# LM_HTR_001.net
KiCad netlist of a schematic drawn in Altium Designer
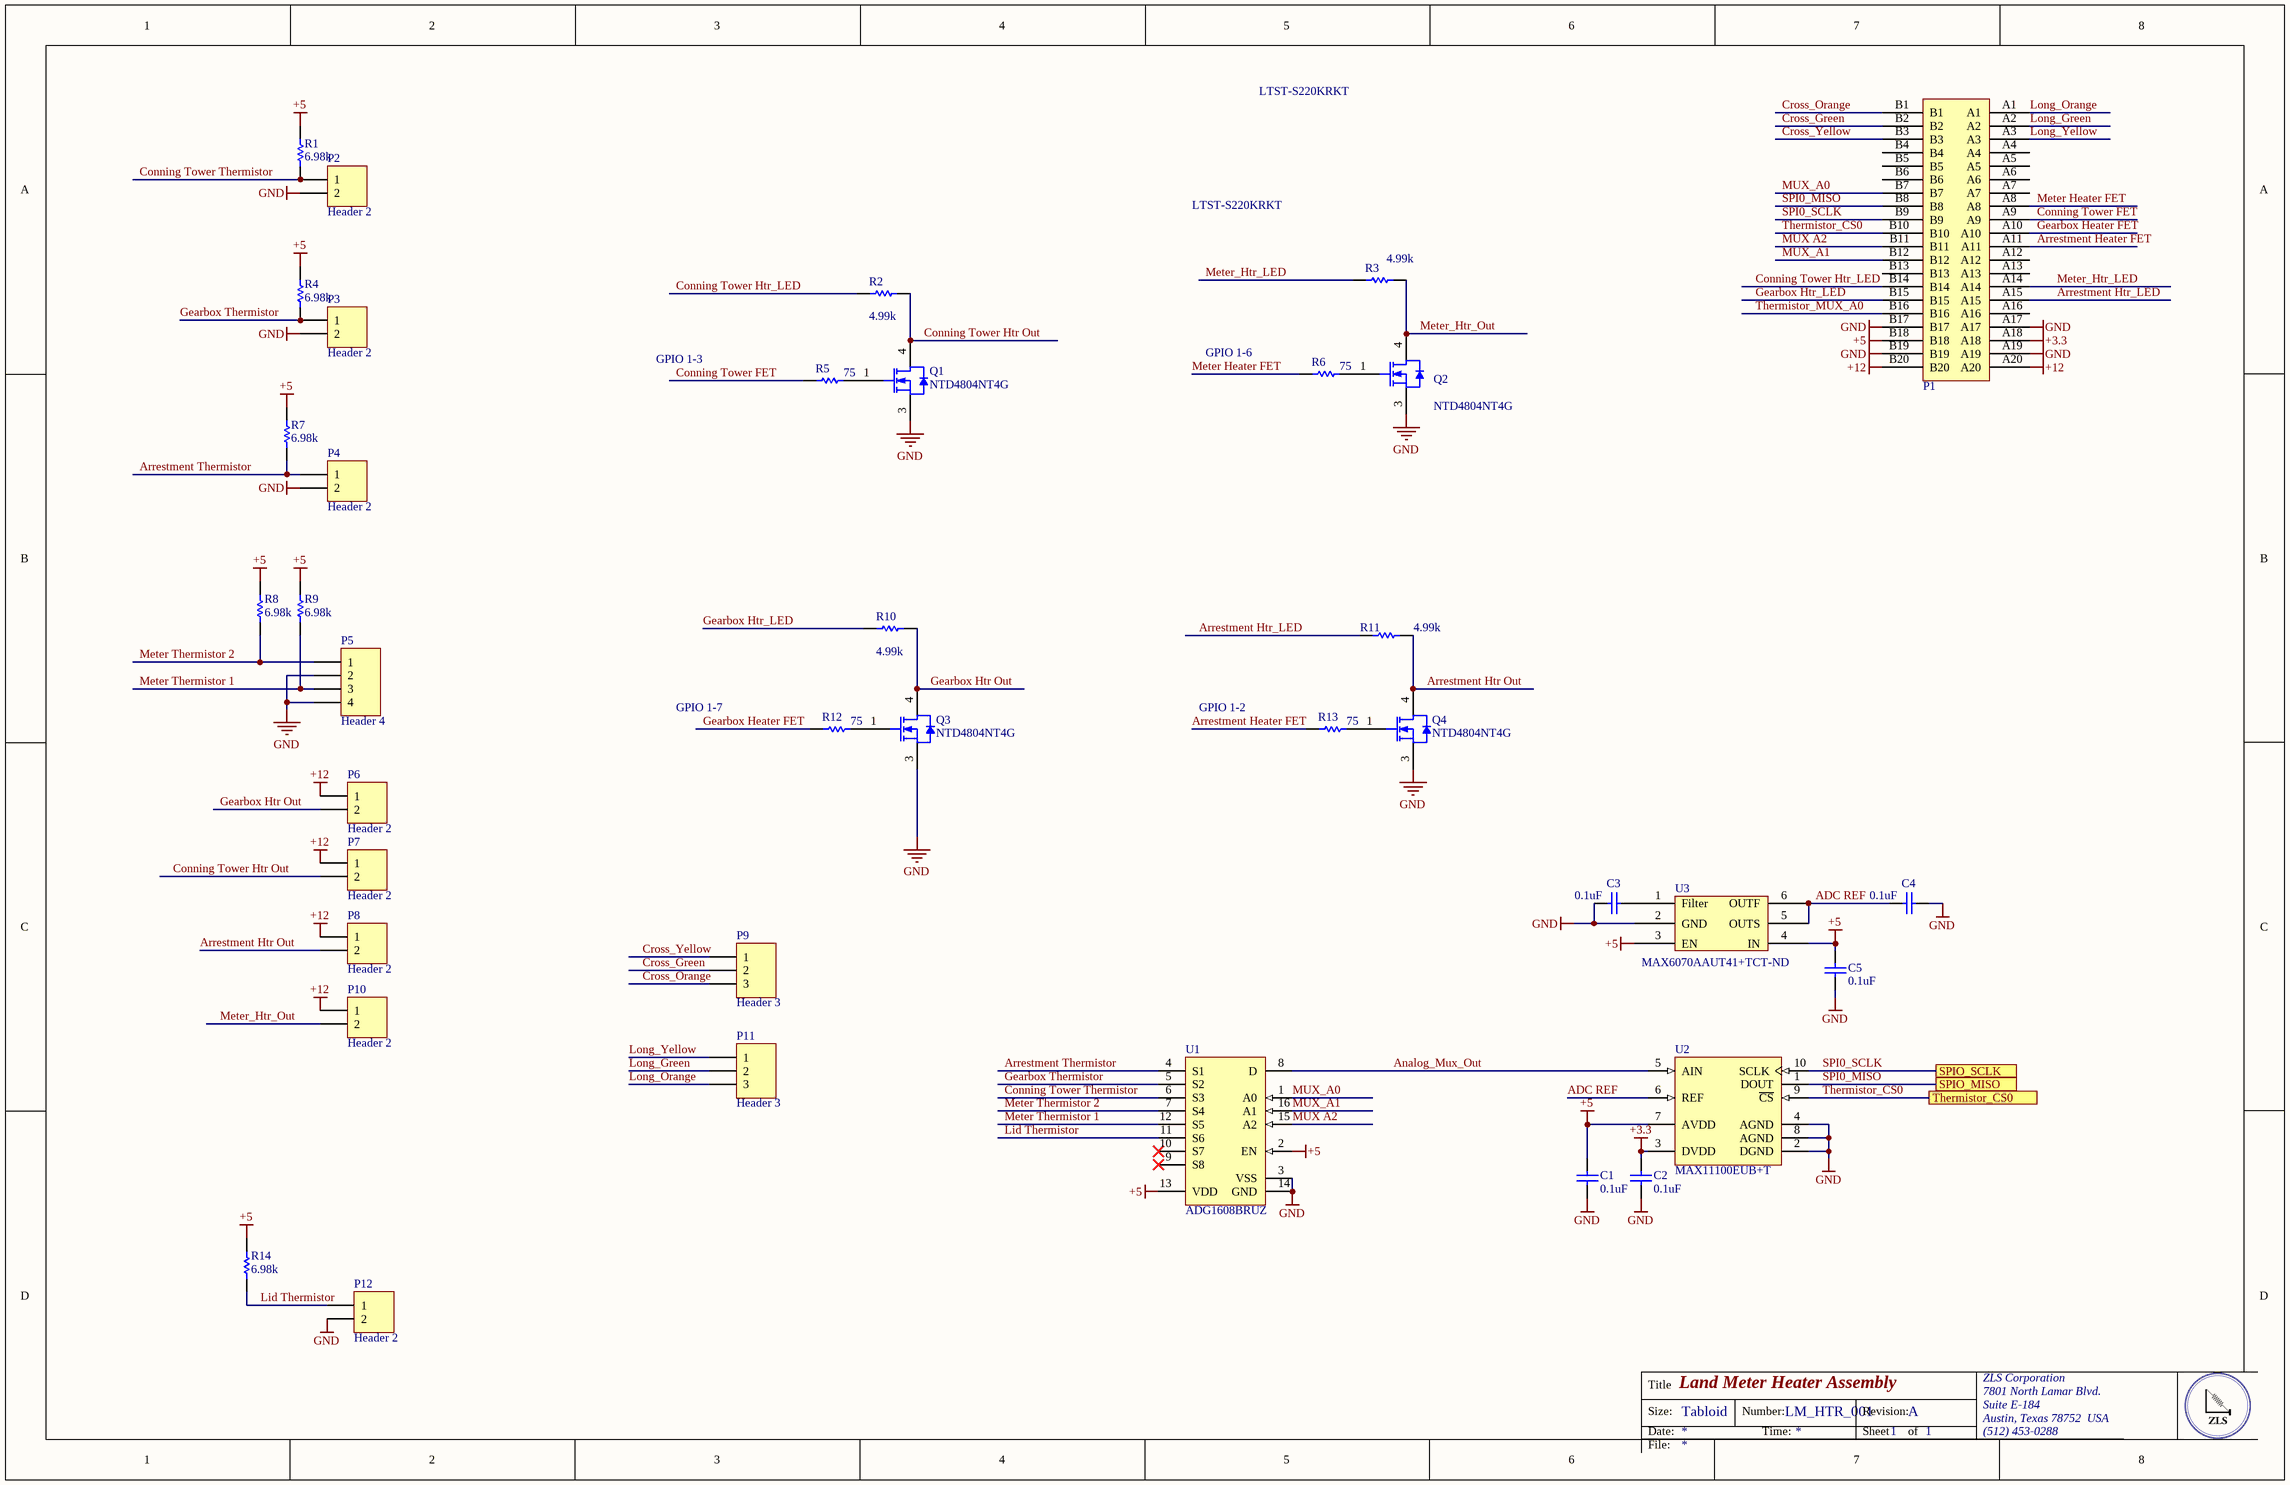
[diagram p0: LM_HTR_001.SchDoc]

(export (version "E")
  (design (tool "Eeschema 10.0.6"))
  (components
    (comp (ref "C1")
      (value "0.1uF")
      (footprint "CAPC0402(1005)60_L")
      (description "CAP CER 0.1UF 10V X7R 0402")
      (fields
        (field (name "MANUFACTURER") "Murata Electronics North America")
        (field (name "MANUFACTURER PART NUMBER") "GRM155R71A104KA01D")
      )
      (libsource (lib "Altium Content Vault") (part "CMP-1034-00252-1"))
    )
    (comp (ref "C2")
      (value "0.1uF")
      (footprint "CAPC0402(1005)60_L")
      (description "CAP CER 0.1UF 10V X7R 0402")
      (fields
        (field (name "MANUFACTURER") "Murata Electronics North America")
        (field (name "MANUFACTURER PART NUMBER") "GRM155R71A104KA01D")
      )
      (libsource (lib "Altium Content Vault") (part "CMP-1034-00252-1"))
    )
    (comp (ref "C3")
      (value "0.1uF")
      (footprint "CAPC0402(1005)60_L")
      (description "CAP CER 0.1UF 10V X7R 0402")
      (fields
        (field (name "MANUFACTURER") "Murata Electronics North America")
        (field (name "MANUFACTURER PART NUMBER") "GRM155R71A104KA01D")
      )
      (libsource (lib "Altium Content Vault") (part "CMP-1034-00252-1"))
    )
    (comp (ref "C4")
      (value "0.1uF")
      (footprint "CAPC0402(1005)60_L")
      (description "CAP CER 0.1UF 10V X7R 0402")
      (fields
        (field (name "MANUFACTURER") "Murata Electronics North America")
        (field (name "MANUFACTURER PART NUMBER") "GRM155R71A104KA01D")
      )
      (libsource (lib "Altium Content Vault") (part "CMP-1034-00252-1"))
    )
    (comp (ref "C5")
      (value "0.1uF")
      (footprint "CAPC0402(1005)60_L")
      (description "CAP CER 0.1UF 10V X7R 0402")
      (fields
        (field (name "MANUFACTURER") "Murata Electronics North America")
        (field (name "MANUFACTURER PART NUMBER") "GRM155R71A104KA01D")
      )
      (libsource (lib "Altium Content Vault") (part "CMP-1034-00252-1"))
    )
    (comp (ref "P1")
      (value "MEC6-120-02-PCB_")
      (footprint "MEC6-120-02-PCB")
      (libsource (lib "ZLS_Schematic_lib") (part "MEC6-120-02-PCB_"))
    )
    (comp (ref "P2")
      (value "Header 2")
      (footprint "HDR1X2")
      (description "Header, 2-Pin")
      (fields (field (name "PUBLISHER") "Altium Limited"))
      (libsource (lib "Miscellaneous Connectors") (part "Header 2"))
    )
    (comp (ref "P3")
      (value "Header 2")
      (footprint "HDR1X2")
      (description "Header, 2-Pin")
      (fields (field (name "PUBLISHER") "Altium Limited"))
      (libsource (lib "Miscellaneous Connectors") (part "Header 2"))
    )
    (comp (ref "P4")
      (value "Header 2")
      (footprint "HDR1X2")
      (description "Header, 2-Pin")
      (fields (field (name "PUBLISHER") "Altium Limited"))
      (libsource (lib "Miscellaneous Connectors") (part "Header 2"))
    )
    (comp (ref "P5")
      (value "Header 4")
      (footprint "HDR1X4")
      (description "Header, 4-Pin")
      (fields (field (name "PUBLISHER") "Altium Limited"))
      (libsource (lib "Miscellaneous Connectors") (part "Header 4"))
    )
    (comp (ref "P6")
      (value "Header 2")
      (footprint "HDR1X2")
      (description "Header, 2-Pin")
      (fields (field (name "PUBLISHER") "Altium Limited"))
      (libsource (lib "Miscellaneous Connectors") (part "Header 2"))
    )
    (comp (ref "P7")
      (value "Header 2")
      (footprint "HDR1X2")
      (description "Header, 2-Pin")
      (fields (field (name "PUBLISHER") "Altium Limited"))
      (libsource (lib "Miscellaneous Connectors") (part "Header 2"))
    )
    (comp (ref "P8")
      (value "Header 2")
      (footprint "HDR1X2")
      (description "Header, 2-Pin")
      (fields (field (name "PUBLISHER") "Altium Limited"))
      (libsource (lib "Miscellaneous Connectors") (part "Header 2"))
    )
    (comp (ref "P9")
      (value "Header 3")
      (footprint "HDR1X3")
      (description "Header, 3-Pin")
      (fields (field (name "PUBLISHER") "Altium Limited"))
      (libsource (lib "Miscellaneous Connectors") (part "Header 3"))
    )
    (comp (ref "P10")
      (value "Header 2")
      (footprint "HDR1X2")
      (description "Header, 2-Pin")
      (fields (field (name "PUBLISHER") "Altium Limited"))
      (libsource (lib "Miscellaneous Connectors") (part "Header 2"))
    )
    (comp (ref "P11")
      (value "Header 3")
      (footprint "HDR1X3")
      (description "Header, 3-Pin")
      (fields (field (name "PUBLISHER") "Altium Limited"))
      (libsource (lib "Miscellaneous Connectors") (part "Header 3"))
    )
    (comp (ref "P12")
      (value "Header 2")
      (footprint "HDR1X2")
      (description "Header, 2-Pin")
      (fields (field (name "PUBLISHER") "Altium Limited"))
      (libsource (lib "Miscellaneous Connectors") (part "Header 2"))
    )
    (comp (ref "Q1")
      (value "NTD4804NT4G")
      (footprint "ONSC-DPAK-3-369AA-01_V")
      (description "Power MOSFET, 30 V, 117 A, Single N-Channel, 3-Pin DPAK, Pb-Free, Tape and Reel")
      (fields (field (name "MANUFACTURER") "On Semiconductor"))
      (libsource (lib "Altium Content Vault") (part "CMP-1058-00341-1"))
    )
    (comp (ref "Q2")
      (value "NTD4804NT4G")
      (footprint "ONSC-DPAK-3-369AA-01_V")
      (description "Power MOSFET, 30 V, 117 A, Single N-Channel, 3-Pin DPAK, Pb-Free, Tape and Reel")
      (fields (field (name "MANUFACTURER") "On Semiconductor"))
      (libsource (lib "Altium Content Vault") (part "CMP-1058-00341-1"))
    )
    (comp (ref "Q3")
      (value "NTD4804NT4G")
      (footprint "ONSC-DPAK-3-369AA-01_V")
      (description "Power MOSFET, 30 V, 117 A, Single N-Channel, 3-Pin DPAK, Pb-Free, Tape and Reel")
      (fields (field (name "MANUFACTURER") "On Semiconductor"))
      (libsource (lib "Altium Content Vault") (part "CMP-1058-00341-1"))
    )
    (comp (ref "Q4")
      (value "NTD4804NT4G")
      (footprint "ONSC-DPAK-3-369AA-01_V")
      (description "Power MOSFET, 30 V, 117 A, Single N-Channel, 3-Pin DPAK, Pb-Free, Tape and Reel")
      (fields (field (name "MANUFACTURER") "On Semiconductor"))
      (libsource (lib "Altium Content Vault") (part "CMP-1058-00341-1"))
    )
    (comp (ref "R1")
      (value "6K98 1% 0805(2012)")
      (footprint "RESC0805(2012)_N")
      (description "6K98 0.125W 1% 0805 (2012 Metric)  SMD")
      (fields
        (field (name "MANUFACTURER") "Vishay Dale")
        (field (name "MANUFACTURER PART NUMBER") "CRCW08056K98FKEA")
        (field (name "RESISTANCE (OHMS)") "6.98k")
      )
      (libsource (lib "Altium Content Vault") (part "CMP-1013-00606-1"))
    )
    (comp (ref "R2")
      (value "~")
      (footprint "RESC0805(2012)_L")
      (fields
        (field (name "MANUFACTURER") "Vishay Dale")
        (field (name "MANUFACTURER PART NUMBER") "CRCW08054K99FKEA")
        (field (name "RESISTANCE (OHMS)") "4.99k")
        (field (name "TOLERANCE") "±1%")
      )
      (libsource (lib "Altium Content Vault") (part "CMP-1013-00393-1"))
    )
    (comp (ref "R3")
      (value "~")
      (footprint "RESC0805(2012)_L")
      (fields
        (field (name "MANUFACTURER") "Vishay Dale")
        (field (name "MANUFACTURER PART NUMBER") "CRCW08054K99FKEA")
        (field (name "RESISTANCE (OHMS)") "4.99k")
        (field (name "TOLERANCE") "±1%")
      )
      (libsource (lib "Altium Content Vault") (part "CMP-1013-00393-1"))
    )
    (comp (ref "R4")
      (value "6K98 1% 0805(2012)")
      (footprint "RESC0805(2012)_N")
      (description "6K98 0.125W 1% 0805 (2012 Metric)  SMD")
      (fields
        (field (name "MANUFACTURER") "Vishay Dale")
        (field (name "MANUFACTURER PART NUMBER") "CRCW08056K98FKEA")
        (field (name "RESISTANCE (OHMS)") "6.98k")
      )
      (libsource (lib "Altium Content Vault") (part "CMP-1013-00606-1"))
    )
    (comp (ref "R5")
      (value "~")
      (footprint "RESC0805(2012)_L")
      (fields
        (field (name "MANUFACTURER") "Vishay Dale")
        (field (name "MANUFACTURER PART NUMBER") "CRCW080575R0FKEA")
        (field (name "RESISTANCE (OHMS)") "75")
        (field (name "TOLERANCE") "±1%")
      )
      (libsource (lib "Altium Content Vault") (part "CMP-1013-00393-1"))
    )
    (comp (ref "R6")
      (value "~")
      (footprint "RESC0805(2012)_L")
      (fields
        (field (name "MANUFACTURER") "Vishay Dale")
        (field (name "MANUFACTURER PART NUMBER") "CRCW080575R0FKEA")
        (field (name "RESISTANCE (OHMS)") "75")
        (field (name "TOLERANCE") "±1%")
      )
      (libsource (lib "Altium Content Vault") (part "CMP-1013-00393-1"))
    )
    (comp (ref "R7")
      (value "6K98 1% 0805(2012)")
      (footprint "RESC0805(2012)_N")
      (description "6K98 0.125W 1% 0805 (2012 Metric)  SMD")
      (fields
        (field (name "MANUFACTURER") "Vishay Dale")
        (field (name "MANUFACTURER PART NUMBER") "CRCW08056K98FKEA")
        (field (name "RESISTANCE (OHMS)") "6.98k")
      )
      (libsource (lib "Altium Content Vault") (part "CMP-1013-00606-1"))
    )
    (comp (ref "R8")
      (value "6K98 1% 0805(2012)")
      (footprint "RESC0805(2012)_N")
      (description "6K98 0.125W 1% 0805 (2012 Metric)  SMD")
      (fields
        (field (name "MANUFACTURER") "Vishay Dale")
        (field (name "MANUFACTURER PART NUMBER") "CRCW08056K98FKEA")
        (field (name "RESISTANCE (OHMS)") "6.98k")
      )
      (libsource (lib "Altium Content Vault") (part "CMP-1013-00606-1"))
    )
    (comp (ref "R9")
      (value "6K98 1% 0805(2012)")
      (footprint "RESC0805(2012)_N")
      (description "6K98 0.125W 1% 0805 (2012 Metric)  SMD")
      (fields
        (field (name "MANUFACTURER") "Vishay Dale")
        (field (name "MANUFACTURER PART NUMBER") "CRCW08056K98FKEA")
        (field (name "RESISTANCE (OHMS)") "6.98k")
      )
      (libsource (lib "Altium Content Vault") (part "CMP-1013-00606-1"))
    )
    (comp (ref "R10")
      (value "~")
      (footprint "RESC0805(2012)_L")
      (fields
        (field (name "MANUFACTURER") "Vishay Dale")
        (field (name "MANUFACTURER PART NUMBER") "CRCW08054K99FKEA")
        (field (name "RESISTANCE (OHMS)") "4.99k")
        (field (name "TOLERANCE") "±1%")
      )
      (libsource (lib "Altium Content Vault") (part "CMP-1013-00393-1"))
    )
    (comp (ref "R11")
      (value "~")
      (footprint "RESC0805(2012)_L")
      (fields
        (field (name "MANUFACTURER") "Vishay Dale")
        (field (name "MANUFACTURER PART NUMBER") "CRCW08054K99FKEA")
        (field (name "RESISTANCE (OHMS)") "4.99k")
        (field (name "TOLERANCE") "±1%")
      )
      (libsource (lib "Altium Content Vault") (part "CMP-1013-00393-1"))
    )
    (comp (ref "R12")
      (value "~")
      (footprint "RESC0805(2012)_L")
      (fields
        (field (name "MANUFACTURER") "Vishay Dale")
        (field (name "MANUFACTURER PART NUMBER") "CRCW080575R0FKEA")
        (field (name "RESISTANCE (OHMS)") "75")
        (field (name "TOLERANCE") "±1%")
      )
      (libsource (lib "Altium Content Vault") (part "CMP-1013-00393-1"))
    )
    (comp (ref "R13")
      (value "~")
      (footprint "RESC0805(2012)_L")
      (fields
        (field (name "MANUFACTURER") "Vishay Dale")
        (field (name "MANUFACTURER PART NUMBER") "CRCW080575R0FKEA")
        (field (name "RESISTANCE (OHMS)") "75")
        (field (name "TOLERANCE") "±1%")
      )
      (libsource (lib "Altium Content Vault") (part "CMP-1013-00393-1"))
    )
    (comp (ref "R14")
      (value "6K98 1% 0805(2012)")
      (footprint "RESC0805(2012)_N")
      (description "6K98 0.125W 1% 0805 (2012 Metric)  SMD")
      (fields
        (field (name "MANUFACTURER") "Vishay Dale")
        (field (name "MANUFACTURER PART NUMBER") "CRCW08056K98FKEA")
        (field (name "RESISTANCE (OHMS)") "6.98k")
      )
      (libsource (lib "Altium Content Vault") (part "CMP-1013-00606-1"))
    )
    (comp (ref "U1")
      (value "ADG1608BRUZ")
      (footprint "ADI-RU-16_M")
      (description "4.5 Ohm Ron, 8-Channel +/-5 V,+12 V, +5 V and +3.3 V Multiplexer, 16-pin SOP (RU-16), Tube")
      (fields (field (name "MANUFACTURER") "Analog Devices"))
      (libsource (lib "Altium Content Vault") (part "ADI-ADG1608-RU-16"))
    )
    (comp (ref "U2")
      (value "MAX11100EUB+T")
      (footprint "U10+2_L")
      (description "16-Bit, +5V, 200ksps ADC with 10uA Shutdown, 10-Pin uMAX, -40°C to +85°C, Pb-Free, Tape and Reel")
      (libsource (lib "Altium Content Vault") (part "CON-ADC-MAX11100-IL10"))
    )
    (comp (ref "U3")
      (value "MAX6070AAUT41+T")
      (footprint "SOT95P280X445-6N")
      (description "IC VREF SERIES 4.096V SOT23")
      (fields
        (field (name "SUPPLIER PART NUMBER 1") "MAX6070AAUT41+TCT-ND")
        (field (name "MANUFACTURER") "Maxim Integrated")
        (field (name "TOLERANCE") "±0.04%")
      )
      (libsource (lib "ZLS_Schematic_lib") (part "MAX6070AAUT41+T"))
    )
  )
  (nets
    (net (code "1") (name "+3.3") (class "Default")
      (node (ref "C2") (pin "1") (pinfunction "1_1") (pintype "passive"))
      (node (ref "P1") (pin "A18") (pinfunction "A18_A18") (pintype "passive"))
      (node (ref "U2") (pin "3") (pinfunction "DVDD_3") (pintype "power_in"))
    )
    (net (code "2") (name "+5") (class "Default")
      (node (ref "C1") (pin "1") (pinfunction "1_1") (pintype "passive"))
      (node (ref "C5") (pin "1") (pinfunction "1_1") (pintype "passive"))
      (node (ref "P1") (pin "B18") (pinfunction "B18_B18") (pintype "passive"))
      (node (ref "R1") (pin "2") (pinfunction "2_2") (pintype "passive"))
      (node (ref "R14") (pin "1") (pinfunction "1_1") (pintype "passive"))
      (node (ref "R4") (pin "2") (pinfunction "2_2") (pintype "passive"))
      (node (ref "R7") (pin "1") (pinfunction "1_1") (pintype "passive"))
      (node (ref "R8") (pin "1") (pinfunction "1_1") (pintype "passive"))
      (node (ref "R9") (pin "2") (pinfunction "2_2") (pintype "passive"))
      (node (ref "U1") (pin "13") (pinfunction "VDD_13") (pintype "power_in"))
      (node (ref "U1") (pin "2") (pinfunction "EN_2") (pintype "input"))
      (node (ref "U2") (pin "7") (pinfunction "AVDD_7") (pintype "power_in"))
      (node (ref "U3") (pin "3") (pinfunction "EN_3") (pintype "passive"))
      (node (ref "U3") (pin "4") (pinfunction "IN_4") (pintype "passive"))
    )
    (net (code "3") (name "+12") (class "Default")
      (node (ref "P1") (pin "A20") (pinfunction "A20_A20") (pintype "passive"))
      (node (ref "P1") (pin "B20") (pinfunction "B20_B20") (pintype "passive"))
      (node (ref "P10") (pin "1") (pinfunction "1_1") (pintype "passive"))
      (node (ref "P6") (pin "1") (pinfunction "1_1") (pintype "passive"))
      (node (ref "P7") (pin "1") (pinfunction "1_1") (pintype "passive"))
      (node (ref "P8") (pin "1") (pinfunction "1_1") (pintype "passive"))
    )
    (net (code "4") (name "/ADC REF") (class "Default")
      (node (ref "C4") (pin "2") (pinfunction "2_2") (pintype "passive"))
      (node (ref "U2") (pin "6") (pinfunction "REF_6") (pintype "input"))
      (node (ref "U3") (pin "5") (pinfunction "OUTS_5") (pintype "passive"))
      (node (ref "U3") (pin "6") (pinfunction "OUTF_6") (pintype "passive"))
    )
    (net (code "5") (name "/Analog_Mux_Out") (class "Default")
      (node (ref "U1") (pin "8") (pinfunction "D_8") (pintype "passive"))
      (node (ref "U2") (pin "5") (pinfunction "AIN_5") (pintype "input"))
    )
    (net (code "6") (name "/Arrestment Heater FET") (class "Default")
      (node (ref "P1") (pin "A11") (pinfunction "A11_A11") (pintype "passive"))
      (node (ref "R13") (pin "1") (pinfunction "1_1") (pintype "passive"))
    )
    (net (code "7") (name "/Arrestment Htr Out") (class "Default")
      (node (ref "P8") (pin "2") (pinfunction "2_2") (pintype "passive"))
      (node (ref "Q4") (pin "4") (pinfunction "D_4") (pintype "passive"))
      (node (ref "R11") (pin "2") (pinfunction "2_2") (pintype "passive"))
    )
    (net (code "8") (name "/Arrestment Htr_LED") (class "Default")
      (node (ref "P1") (pin "A15") (pinfunction "A15_A15") (pintype "passive"))
      (node (ref "R11") (pin "1") (pinfunction "1_1") (pintype "passive"))
    )
    (net (code "9") (name "/Arrestment Thermistor") (class "Default")
      (node (ref "P4") (pin "1") (pinfunction "1_1") (pintype "passive"))
      (node (ref "R7") (pin "2") (pinfunction "2_2") (pintype "passive"))
      (node (ref "U1") (pin "4") (pinfunction "S1_4") (pintype "passive"))
    )
    (net (code "10") (name "/Conning Tower FET") (class "Default")
      (node (ref "P1") (pin "A9") (pinfunction "A9_A9") (pintype "passive"))
      (node (ref "R5") (pin "1") (pinfunction "1_1") (pintype "passive"))
    )
    (net (code "11") (name "/Conning Tower Htr Out") (class "Default")
      (node (ref "P7") (pin "2") (pinfunction "2_2") (pintype "passive"))
      (node (ref "Q1") (pin "4") (pinfunction "D_4") (pintype "passive"))
      (node (ref "R2") (pin "1") (pinfunction "1_1") (pintype "passive"))
    )
    (net (code "12") (name "/Conning Tower Htr_LED") (class "Default")
      (node (ref "P1") (pin "B14") (pinfunction "B14_B14") (pintype "passive"))
      (node (ref "R2") (pin "2") (pinfunction "2_2") (pintype "passive"))
    )
    (net (code "13") (name "/Conning Tower Thermistor") (class "Default")
      (node (ref "P2") (pin "1") (pinfunction "1_1") (pintype "passive"))
      (node (ref "R1") (pin "1") (pinfunction "1_1") (pintype "passive"))
      (node (ref "U1") (pin "6") (pinfunction "S3_6") (pintype "passive"))
    )
    (net (code "14") (name "/Cross_Green") (class "Default")
      (node (ref "P1") (pin "B2") (pinfunction "B2_B2") (pintype "passive"))
      (node (ref "P9") (pin "2") (pinfunction "2_2") (pintype "passive"))
    )
    (net (code "15") (name "/Cross_Orange") (class "Default")
      (node (ref "P1") (pin "B1") (pinfunction "B1_B1") (pintype "passive"))
      (node (ref "P9") (pin "3") (pinfunction "3_3") (pintype "passive"))
    )
    (net (code "16") (name "/Cross_Yellow") (class "Default")
      (node (ref "P1") (pin "B3") (pinfunction "B3_B3") (pintype "passive"))
      (node (ref "P9") (pin "1") (pinfunction "1_1") (pintype "passive"))
    )
    (net (code "17") (name "/Gearbox Heater FET") (class "Default")
      (node (ref "P1") (pin "A10") (pinfunction "A10_A10") (pintype "passive"))
      (node (ref "R12") (pin "1") (pinfunction "1_1") (pintype "passive"))
    )
    (net (code "18") (name "/Gearbox Htr Out") (class "Default")
      (node (ref "P6") (pin "2") (pinfunction "2_2") (pintype "passive"))
      (node (ref "Q3") (pin "4") (pinfunction "D_4") (pintype "passive"))
      (node (ref "R10") (pin "1") (pinfunction "1_1") (pintype "passive"))
    )
    (net (code "19") (name "/Gearbox Htr_LED") (class "Default")
      (node (ref "P1") (pin "B15") (pinfunction "B15_B15") (pintype "passive"))
      (node (ref "R10") (pin "2") (pinfunction "2_2") (pintype "passive"))
    )
    (net (code "20") (name "/Gearbox Thermistor") (class "Default")
      (node (ref "P3") (pin "1") (pinfunction "1_1") (pintype "passive"))
      (node (ref "R4") (pin "1") (pinfunction "1_1") (pintype "passive"))
      (node (ref "U1") (pin "5") (pinfunction "S2_5") (pintype "passive"))
    )
    (net (code "21") (name "/Lid Thermistor") (class "Default")
      (node (ref "P12") (pin "1") (pinfunction "1_1") (pintype "passive"))
      (node (ref "R14") (pin "2") (pinfunction "2_2") (pintype "passive"))
      (node (ref "U1") (pin "11") (pinfunction "S6_11") (pintype "passive"))
    )
    (net (code "22") (name "/Long_Green") (class "Default")
      (node (ref "P1") (pin "A2") (pinfunction "A2_A2") (pintype "passive"))
      (node (ref "P11") (pin "2") (pinfunction "2_2") (pintype "passive"))
    )
    (net (code "23") (name "/Long_Orange") (class "Default")
      (node (ref "P1") (pin "A1") (pinfunction "A1_A1") (pintype "passive"))
      (node (ref "P11") (pin "3") (pinfunction "3_3") (pintype "passive"))
    )
    (net (code "24") (name "/Long_Yellow") (class "Default")
      (node (ref "P1") (pin "A3") (pinfunction "A3_A3") (pintype "passive"))
      (node (ref "P11") (pin "1") (pinfunction "1_1") (pintype "passive"))
    )
    (net (code "25") (name "/MUX A2") (class "Default")
      (node (ref "P1") (pin "B11") (pinfunction "B11_B11") (pintype "passive"))
      (node (ref "U1") (pin "15") (pinfunction "A2_15") (pintype "input"))
    )
    (net (code "26") (name "/MUX_A0") (class "Default")
      (node (ref "P1") (pin "B7") (pinfunction "B7_B7") (pintype "passive"))
      (node (ref "U1") (pin "1") (pinfunction "A0_1") (pintype "input"))
    )
    (net (code "27") (name "/MUX_A1") (class "Default")
      (node (ref "P1") (pin "B12") (pinfunction "B12_B12") (pintype "passive"))
      (node (ref "U1") (pin "16") (pinfunction "A1_16") (pintype "input"))
    )
    (net (code "28") (name "/Meter Heater FET") (class "Default")
      (node (ref "P1") (pin "A8") (pinfunction "A8_A8") (pintype "passive"))
      (node (ref "R6") (pin "1") (pinfunction "1_1") (pintype "passive"))
    )
    (net (code "29") (name "/Meter Thermistor 1") (class "Default")
      (node (ref "P5") (pin "3") (pinfunction "3_3") (pintype "passive"))
      (node (ref "R9") (pin "1") (pinfunction "1_1") (pintype "passive"))
      (node (ref "U1") (pin "12") (pinfunction "S5_12") (pintype "passive"))
    )
    (net (code "30") (name "/Meter Thermistor 2") (class "Default")
      (node (ref "P5") (pin "1") (pinfunction "1_1") (pintype "passive"))
      (node (ref "R8") (pin "2") (pinfunction "2_2") (pintype "passive"))
      (node (ref "U1") (pin "7") (pinfunction "S4_7") (pintype "passive"))
    )
    (net (code "31") (name "/Meter_Htr_LED") (class "Default")
      (node (ref "P1") (pin "A14") (pinfunction "A14_A14") (pintype "passive"))
      (node (ref "R3") (pin "1") (pinfunction "1_1") (pintype "passive"))
    )
    (net (code "32") (name "/Meter_Htr_Out") (class "Default")
      (node (ref "P10") (pin "2") (pinfunction "2_2") (pintype "passive"))
      (node (ref "Q2") (pin "4") (pinfunction "D_4") (pintype "passive"))
      (node (ref "R3") (pin "2") (pinfunction "2_2") (pintype "passive"))
    )
    (net (code "33") (name "/SPI0_MISO") (class "Default")
      (node (ref "P1") (pin "B8") (pinfunction "B8_B8") (pintype "passive"))
      (node (ref "U2") (pin "1") (pinfunction "DOUT_1") (pintype "tri_state"))
    )
    (net (code "34") (name "/SPI0_SCLK") (class "Default")
      (node (ref "P1") (pin "B9") (pinfunction "B9_B9") (pintype "passive"))
      (node (ref "U2") (pin "10") (pinfunction "SCLK_10") (pintype "input"))
    )
    (net (code "35") (name "/Thermistor_CS0") (class "Default")
      (node (ref "P1") (pin "B10") (pinfunction "B10_B10") (pintype "passive"))
      (node (ref "U2") (pin "9") (pinfunction "~{CS}_9") (pintype "input"))
    )
    (net (code "36") (name "/Thermistor_MUX_A0") (class "Default")
      (node (ref "P1") (pin "B16") (pinfunction "B16_B16") (pintype "passive"))
    )
    (net (code "37") (name "GND") (class "Default")
      (node (ref "C1") (pin "2") (pinfunction "2_2") (pintype "passive"))
      (node (ref "C2") (pin "2") (pinfunction "2_2") (pintype "passive"))
      (node (ref "C3") (pin "2") (pinfunction "2_2") (pintype "passive"))
      (node (ref "C4") (pin "1") (pinfunction "1_1") (pintype "passive"))
      (node (ref "C5") (pin "2") (pinfunction "2_2") (pintype "passive"))
      (node (ref "P1") (pin "A17") (pinfunction "A17_A17") (pintype "passive"))
      (node (ref "P1") (pin "A19") (pinfunction "A19_A19") (pintype "passive"))
      (node (ref "P1") (pin "B17") (pinfunction "B17_B17") (pintype "passive"))
      (node (ref "P1") (pin "B19") (pinfunction "B19_B19") (pintype "passive"))
      (node (ref "P12") (pin "2") (pinfunction "2_2") (pintype "passive"))
      (node (ref "P2") (pin "2") (pinfunction "2_2") (pintype "passive"))
      (node (ref "P3") (pin "2") (pinfunction "2_2") (pintype "passive"))
      (node (ref "P4") (pin "2") (pinfunction "2_2") (pintype "passive"))
      (node (ref "P5") (pin "2") (pinfunction "2_2") (pintype "passive"))
      (node (ref "P5") (pin "4") (pinfunction "4_4") (pintype "passive"))
      (node (ref "Q1") (pin "3") (pinfunction "S_3") (pintype "passive"))
      (node (ref "Q2") (pin "3") (pinfunction "S_3") (pintype "passive"))
      (node (ref "Q3") (pin "3") (pinfunction "S_3") (pintype "passive"))
      (node (ref "Q4") (pin "3") (pinfunction "S_3") (pintype "passive"))
      (node (ref "U1") (pin "14") (pinfunction "GND_14") (pintype "power_in"))
      (node (ref "U1") (pin "3") (pinfunction "VSS_3") (pintype "power_in"))
      (node (ref "U2") (pin "2") (pinfunction "DGND_2") (pintype "power_in"))
      (node (ref "U2") (pin "4") (pinfunction "AGND_4") (pintype "power_in"))
      (node (ref "U2") (pin "8") (pinfunction "AGND_8") (pintype "power_in"))
      (node (ref "U3") (pin "2") (pinfunction "GND_2") (pintype "passive"))
    )
    (net (code "38") (name "Net-(Q1-G)") (class "Default")
      (node (ref "Q1") (pin "1") (pinfunction "G_1") (pintype "passive"))
      (node (ref "R5") (pin "2") (pinfunction "2_2") (pintype "passive"))
    )
    (net (code "39") (name "Net-(Q2-G)") (class "Default")
      (node (ref "Q2") (pin "1") (pinfunction "G_1") (pintype "passive"))
      (node (ref "R6") (pin "2") (pinfunction "2_2") (pintype "passive"))
    )
    (net (code "40") (name "Net-(Q3-G)") (class "Default")
      (node (ref "Q3") (pin "1") (pinfunction "G_1") (pintype "passive"))
      (node (ref "R12") (pin "2") (pinfunction "2_2") (pintype "passive"))
    )
    (net (code "41") (name "Net-(Q4-G)") (class "Default")
      (node (ref "Q4") (pin "1") (pinfunction "G_1") (pintype "passive"))
      (node (ref "R13") (pin "2") (pinfunction "2_2") (pintype "passive"))
    )
    (net (code "42") (name "Net-(U3-Filter)") (class "Default")
      (node (ref "C3") (pin "1") (pinfunction "1_1") (pintype "passive"))
      (node (ref "U3") (pin "1") (pinfunction "Filter_1") (pintype "passive"))
    )
    (net (code "43") (name "unconnected-(P1-PadA4)") (class "Default")
      (node (ref "P1") (pin "A4") (pinfunction "A4_A4") (pintype "passive"))
    )
    (net (code "44") (name "unconnected-(P1-PadA5)") (class "Default")
      (node (ref "P1") (pin "A5") (pinfunction "A5_A5") (pintype "passive"))
    )
    (net (code "45") (name "unconnected-(P1-PadA6)") (class "Default")
      (node (ref "P1") (pin "A6") (pinfunction "A6_A6") (pintype "passive"))
    )
    (net (code "46") (name "unconnected-(P1-PadA7)") (class "Default")
      (node (ref "P1") (pin "A7") (pinfunction "A7_A7") (pintype "passive"))
    )
    (net (code "47") (name "unconnected-(P1-PadA12)") (class "Default")
      (node (ref "P1") (pin "A12") (pinfunction "A12_A12") (pintype "passive"))
    )
    (net (code "48") (name "unconnected-(P1-PadA13)") (class "Default")
      (node (ref "P1") (pin "A13") (pinfunction "A13_A13") (pintype "passive"))
    )
    (net (code "49") (name "unconnected-(P1-PadA16)") (class "Default")
      (node (ref "P1") (pin "A16") (pinfunction "A16_A16") (pintype "passive"))
    )
    (net (code "50") (name "unconnected-(P1-PadB4)") (class "Default")
      (node (ref "P1") (pin "B4") (pinfunction "B4_B4") (pintype "passive"))
    )
    (net (code "51") (name "unconnected-(P1-PadB5)") (class "Default")
      (node (ref "P1") (pin "B5") (pinfunction "B5_B5") (pintype "passive"))
    )
    (net (code "52") (name "unconnected-(P1-PadB6)") (class "Default")
      (node (ref "P1") (pin "B6") (pinfunction "B6_B6") (pintype "passive"))
    )
    (net (code "53") (name "unconnected-(P1-PadB13)") (class "Default")
      (node (ref "P1") (pin "B13") (pinfunction "B13_B13") (pintype "passive"))
    )
    (net (code "54") (name "unconnected-(U1-S7-Pad10)") (class "Default")
      (node (ref "U1") (pin "10") (pinfunction "S7_10") (pintype "passive+no_connect"))
    )
    (net (code "55") (name "unconnected-(U1-S8-Pad9)") (class "Default")
      (node (ref "U1") (pin "9") (pinfunction "S8_9") (pintype "passive+no_connect"))
    )
  )
)
